# Controller.net
KiCad netlist of a schematic drawn in EasyEDA
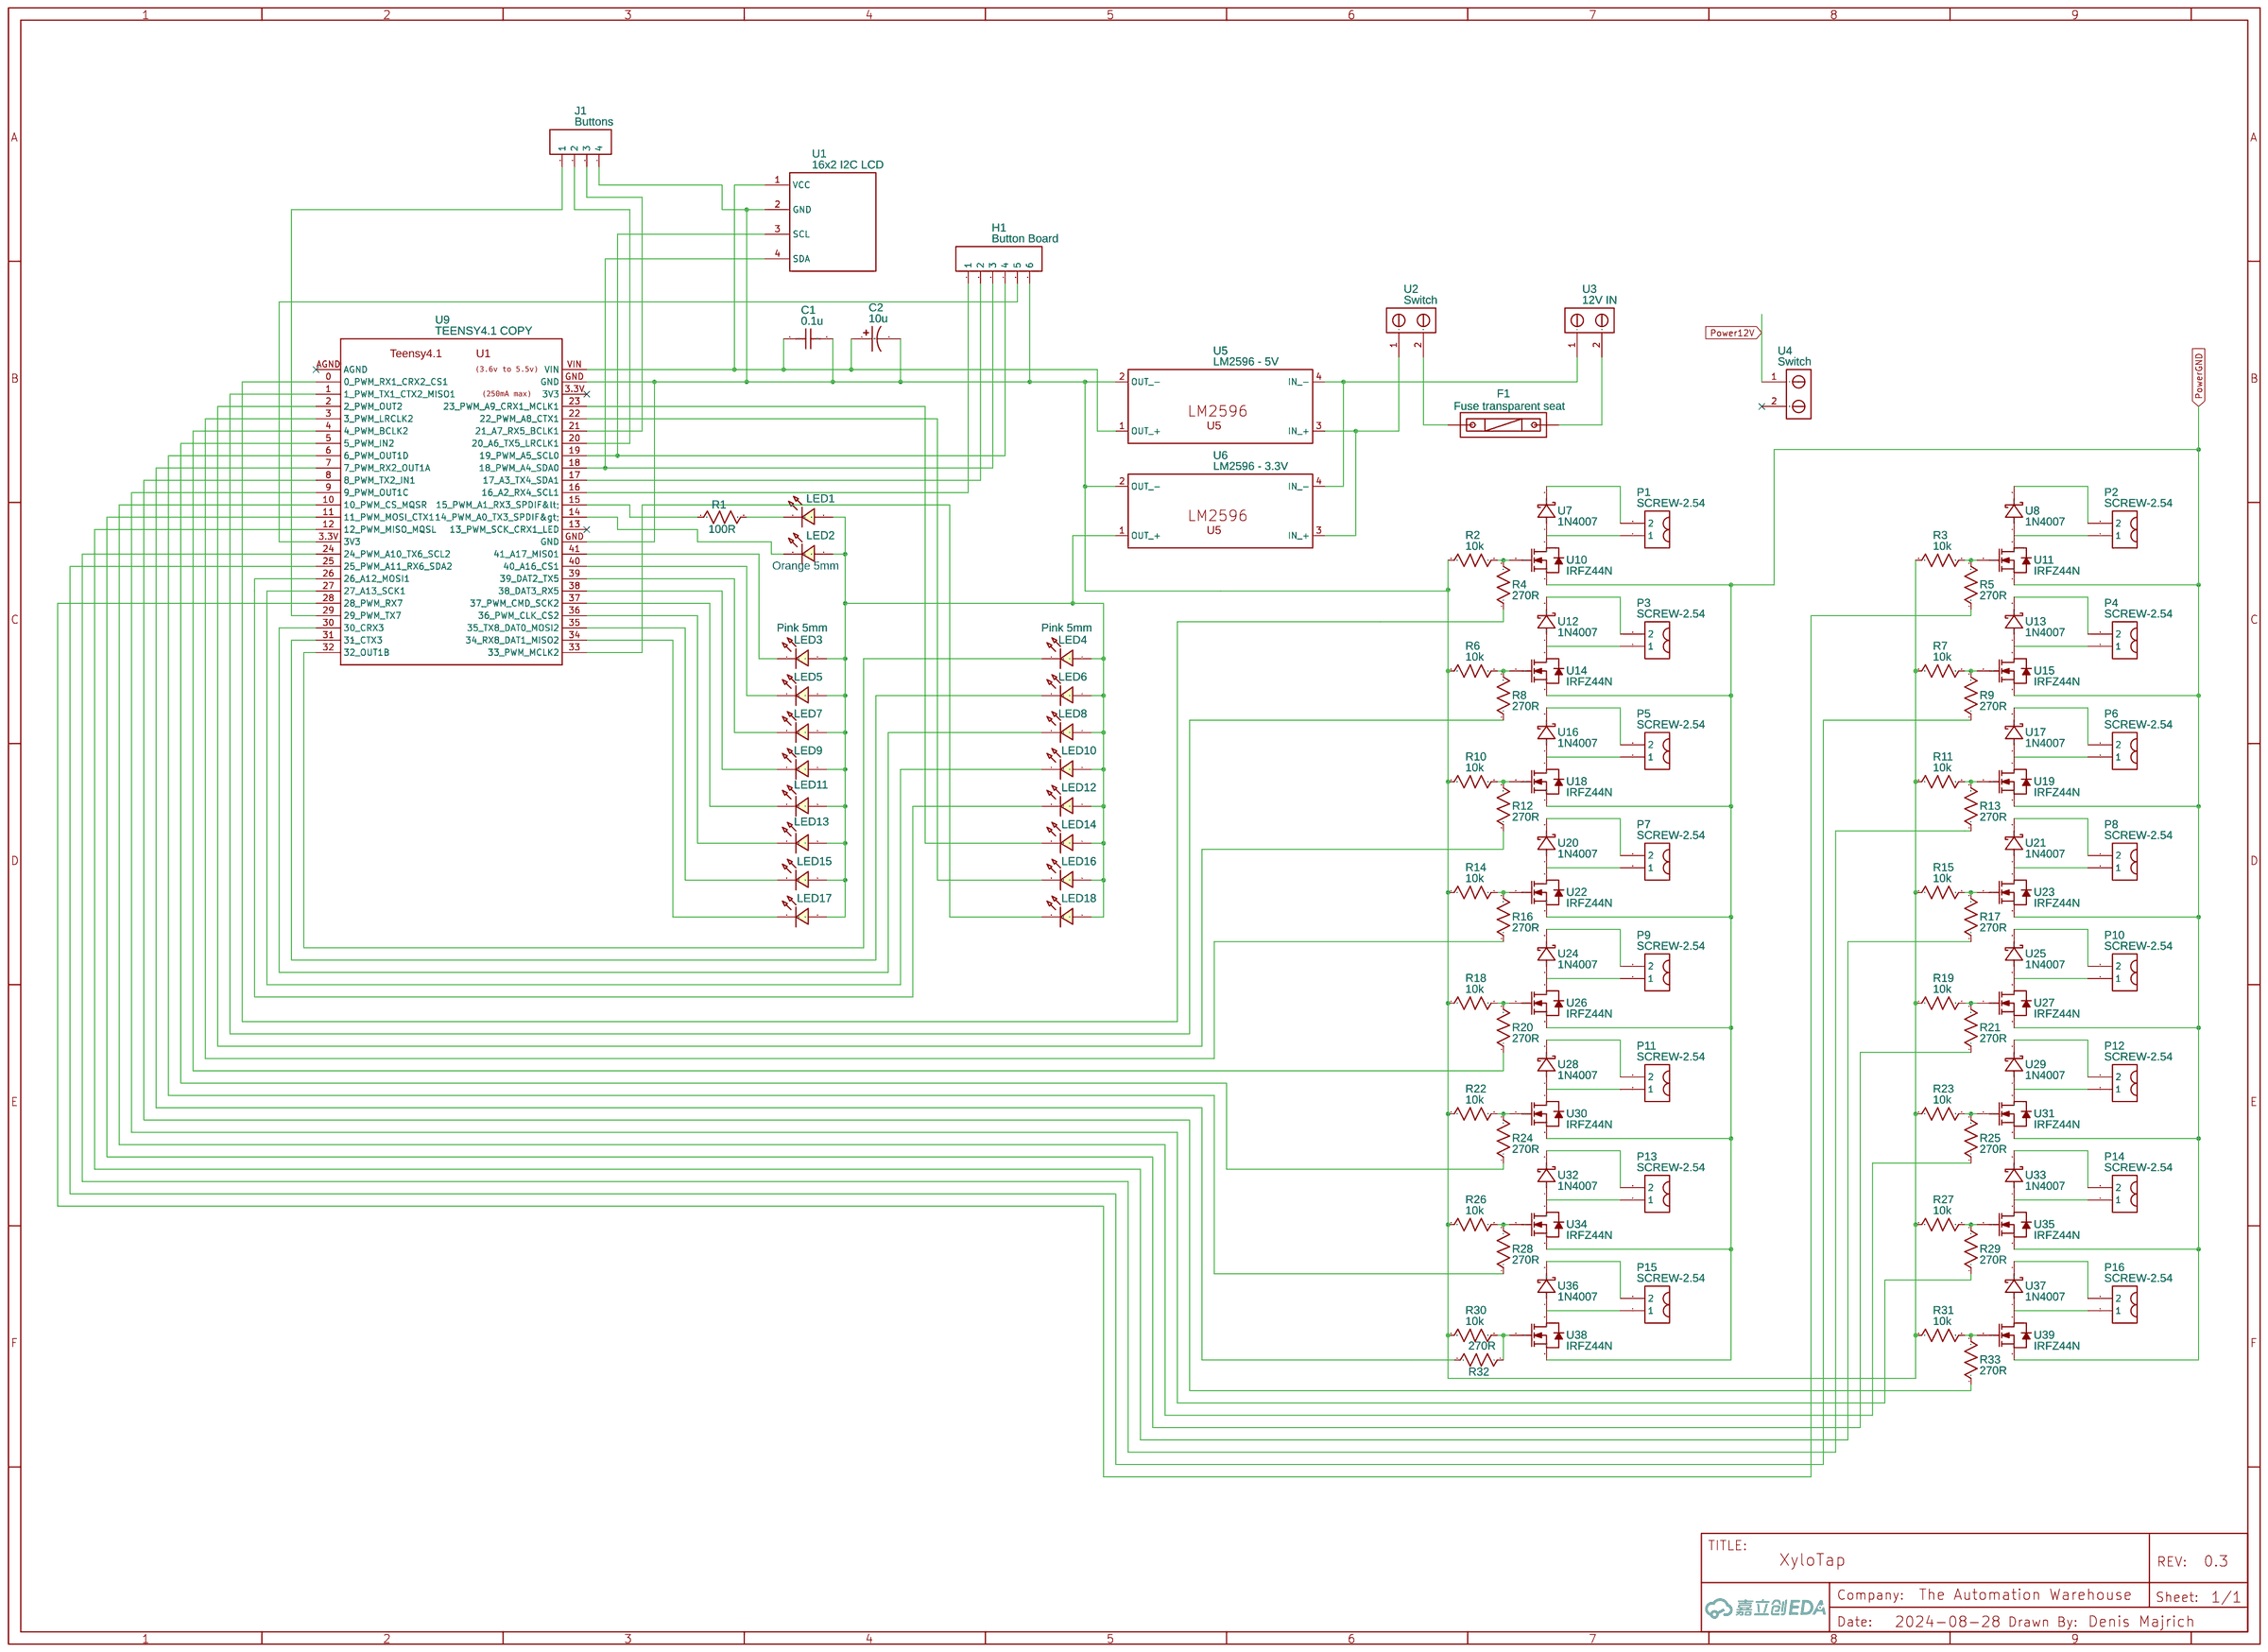
[diagram p0: schematic sheet]

(export (version "E")
  (design (tool "Eeschema 10.0.6"))
  (components
    (comp (ref "C1") (value "0.1u") (libsource (lib "") (part "C_RAD-0.1_US")))
    (comp (ref "C2") (value "10u") (libsource (lib "") (part "CE_TH_D5.0×F2.0_US")))
    (comp (ref "F1")
      (value "Fuse transparent seat")
      (fields (field (name "Manufacturer Part") "保险丝透明座") (field (name "Manufacturer") "xcfuse(旭程)"))
      (libsource (lib "") (part "Fuse transparent seat"))
    )
    (comp (ref "H1")
      (value "Button Board")
      (fields (field (name "BOM_Supplier Part") "C40877"))
      (libsource (lib "") (part "HDR-F-2.54_1x6"))
    )
    (comp (ref "J1")
      (value "Buttons")
      (fields (field (name "BOM_Supplier Part") "C124378"))
      (libsource (lib "") (part "HDR-M-2.54_1x4"))
    )
    (comp (ref "LED1") (value "Pink 5mm") (libsource (lib "") (part "LED-TH-5mm_B")))
    (comp (ref "LED2") (value "Pink 5mm") (libsource (lib "") (part "LED-TH-5mm_B")))
    (comp (ref "LED3") (value "Pink 5mm") (libsource (lib "") (part "LED-TH-5mm_B")))
    (comp (ref "LED4") (value "Pink 5mm") (libsource (lib "") (part "LED-TH-5mm_B")))
    (comp (ref "LED5") (value "Pink 5mm") (libsource (lib "") (part "LED-TH-5mm_B")))
    (comp (ref "LED6") (value "Pink 5mm") (libsource (lib "") (part "LED-TH-5mm_B")))
    (comp (ref "LED7") (value "Pink 5mm") (libsource (lib "") (part "LED-TH-5mm_B")))
    (comp (ref "LED8") (value "Pink 5mm") (libsource (lib "") (part "LED-TH-5mm_B")))
    (comp (ref "LED9") (value "Pink 5mm") (libsource (lib "") (part "LED-TH-5mm_B")))
    (comp (ref "LED10") (value "Pink 5mm") (libsource (lib "") (part "LED-TH-5mm_B")))
    (comp (ref "LED11") (value "Pink 5mm") (libsource (lib "") (part "LED-TH-5mm_B")))
    (comp (ref "LED12") (value "Pink 5mm") (libsource (lib "") (part "LED-TH-5mm_B")))
    (comp (ref "LED13") (value "Pink 5mm") (libsource (lib "") (part "LED-TH-5mm_B")))
    (comp (ref "LED14") (value "Pink 5mm") (libsource (lib "") (part "LED-TH-5mm_B")))
    (comp (ref "LED15") (value "Pink 5mm") (libsource (lib "") (part "LED-TH-5mm_B")))
    (comp (ref "LED16") (value "Pink 5mm") (libsource (lib "") (part "LED-TH-5mm_B")))
    (comp (ref "LED17") (value "Pink 5mm") (libsource (lib "") (part "LED-TH-5mm_B")))
    (comp (ref "LED18") (value "Pink 5mm") (libsource (lib "") (part "LED-TH-5mm_B")))
    (comp (ref "P1") (value "SCREW-2.54") (libsource (lib "") (part "PCBSCREW-2.54-2P")))
    (comp (ref "P2") (value "SCREW-2.54") (libsource (lib "") (part "PCBSCREW-2.54-2P")))
    (comp (ref "P3") (value "SCREW-2.54") (libsource (lib "") (part "PCBSCREW-2.54-2P")))
    (comp (ref "P4") (value "SCREW-2.54") (libsource (lib "") (part "PCBSCREW-2.54-2P")))
    (comp (ref "P5") (value "SCREW-2.54") (libsource (lib "") (part "PCBSCREW-2.54-2P")))
    (comp (ref "P6") (value "SCREW-2.54") (libsource (lib "") (part "PCBSCREW-2.54-2P")))
    (comp (ref "P7") (value "SCREW-2.54") (libsource (lib "") (part "PCBSCREW-2.54-2P")))
    (comp (ref "P8") (value "SCREW-2.54") (libsource (lib "") (part "PCBSCREW-2.54-2P")))
    (comp (ref "P9") (value "SCREW-2.54") (libsource (lib "") (part "PCBSCREW-2.54-2P")))
    (comp (ref "P10") (value "SCREW-2.54") (libsource (lib "") (part "PCBSCREW-2.54-2P")))
    (comp (ref "P11") (value "SCREW-2.54") (libsource (lib "") (part "PCBSCREW-2.54-2P")))
    (comp (ref "P12") (value "SCREW-2.54") (libsource (lib "") (part "PCBSCREW-2.54-2P")))
    (comp (ref "P13") (value "SCREW-2.54") (libsource (lib "") (part "PCBSCREW-2.54-2P")))
    (comp (ref "P14") (value "SCREW-2.54") (libsource (lib "") (part "PCBSCREW-2.54-2P")))
    (comp (ref "P15") (value "SCREW-2.54") (libsource (lib "") (part "PCBSCREW-2.54-2P")))
    (comp (ref "P16") (value "SCREW-2.54") (libsource (lib "") (part "PCBSCREW-2.54-2P")))
    (comp (ref "R1") (value "100R") (libsource (lib "") (part "R_AXIAL-0.4_US_1")))
    (comp (ref "R2") (value "10k") (libsource (lib "") (part "R_AXIAL-0.4_US_1")))
    (comp (ref "R3") (value "10k") (libsource (lib "") (part "R_AXIAL-0.4_US_1")))
    (comp (ref "R4") (value "270R") (libsource (lib "") (part "R_AXIAL-0.4_US")))
    (comp (ref "R5") (value "270R") (libsource (lib "") (part "R_AXIAL-0.4_US")))
    (comp (ref "R6") (value "10k") (libsource (lib "") (part "R_AXIAL-0.4_US_1")))
    (comp (ref "R7") (value "10k") (libsource (lib "") (part "R_AXIAL-0.4_US_1")))
    (comp (ref "R8") (value "270R") (libsource (lib "") (part "R_AXIAL-0.4_US")))
    (comp (ref "R9") (value "270R") (libsource (lib "") (part "R_AXIAL-0.4_US")))
    (comp (ref "R10") (value "10k") (libsource (lib "") (part "R_AXIAL-0.4_US_1")))
    (comp (ref "R11") (value "10k") (libsource (lib "") (part "R_AXIAL-0.4_US_1")))
    (comp (ref "R12") (value "270R") (libsource (lib "") (part "R_AXIAL-0.4_US")))
    (comp (ref "R13") (value "270R") (libsource (lib "") (part "R_AXIAL-0.4_US")))
    (comp (ref "R14") (value "10k") (libsource (lib "") (part "R_AXIAL-0.4_US_1")))
    (comp (ref "R15") (value "10k") (libsource (lib "") (part "R_AXIAL-0.4_US_1")))
    (comp (ref "R16") (value "270R") (libsource (lib "") (part "R_AXIAL-0.4_US")))
    (comp (ref "R17") (value "270R") (libsource (lib "") (part "R_AXIAL-0.4_US")))
    (comp (ref "R18") (value "10k") (libsource (lib "") (part "R_AXIAL-0.4_US_1")))
    (comp (ref "R19") (value "10k") (libsource (lib "") (part "R_AXIAL-0.4_US_1")))
    (comp (ref "R20") (value "270R") (libsource (lib "") (part "R_AXIAL-0.4_US")))
    (comp (ref "R21") (value "270R") (libsource (lib "") (part "R_AXIAL-0.4_US")))
    (comp (ref "R22") (value "10k") (libsource (lib "") (part "R_AXIAL-0.4_US_1")))
    (comp (ref "R23") (value "10k") (libsource (lib "") (part "R_AXIAL-0.4_US_1")))
    (comp (ref "R24") (value "270R") (libsource (lib "") (part "R_AXIAL-0.4_US")))
    (comp (ref "R25") (value "270R") (libsource (lib "") (part "R_AXIAL-0.4_US")))
    (comp (ref "R26") (value "10k") (libsource (lib "") (part "R_AXIAL-0.4_US_1")))
    (comp (ref "R27") (value "10k") (libsource (lib "") (part "R_AXIAL-0.4_US_1")))
    (comp (ref "R28") (value "270R") (libsource (lib "") (part "R_AXIAL-0.4_US")))
    (comp (ref "R29") (value "270R") (libsource (lib "") (part "R_AXIAL-0.4_US")))
    (comp (ref "R30") (value "10k") (libsource (lib "") (part "R_AXIAL-0.4_US_1")))
    (comp (ref "R31") (value "10k") (libsource (lib "") (part "R_AXIAL-0.4_US_1")))
    (comp (ref "R32") (value "270R") (libsource (lib "") (part "R_AXIAL-0.4_US_2")))
    (comp (ref "R33") (value "270R") (libsource (lib "") (part "R_AXIAL-0.4_US")))
    (comp (ref "U1") (value "16x2 I2C LCD") (libsource (lib "") (part "16x2 i2c LCD no mount on PCB")))
    (comp (ref "U2") (value "Switch") (libsource (lib "") (part "Terminal_x2_5mm")))
    (comp (ref "U3") (value "12V IN") (libsource (lib "") (part "Terminal_x2_5mm")))
    (comp (ref "U4") (value "Switch") (libsource (lib "") (part "Terminal_x2_5mm_1")))
    (comp (ref "U5")
      (value "LM2596 - 5V")
      (fields (field (name "BOM_Manufacturer Part") "LM2596ALEX"))
      (libsource (lib "") (part "LM2596ALEX"))
    )
    (comp (ref "U6")
      (value "LM2596 - 3.3V")
      (fields (field (name "BOM_Manufacturer Part") "LM2596ALEX"))
      (libsource (lib "") (part "LM2596ALEX"))
    )
    (comp (ref "U7")
      (value "1N4007")
      (fields (field (name "Manufacturer Part") "1N4007-DIODE"))
      (libsource (lib "") (part "1N4007-DIODE"))
    )
    (comp (ref "U8")
      (value "1N4007")
      (fields (field (name "Manufacturer Part") "1N4007-DIODE"))
      (libsource (lib "") (part "1N4007-DIODE"))
    )
    (comp (ref "U9")
      (value "TEENSY4.1 COPY")
      (fields (field (name "BOM_Manufacturer Part") "Teensy4.1"))
      (libsource (lib "") (part "TEENSY4.1 COPY"))
    )
    (comp (ref "U10")
      (value "IRFZ44N")
      (fields (field (name "Manufacturer") "minos(迈诺斯)"))
      (libsource (lib "") (part "IRFZ44N"))
    )
    (comp (ref "U11")
      (value "IRFZ44N")
      (fields (field (name "Manufacturer") "minos(迈诺斯)"))
      (libsource (lib "") (part "IRFZ44N"))
    )
    (comp (ref "U12")
      (value "1N4007")
      (fields (field (name "Manufacturer Part") "1N4007-DIODE"))
      (libsource (lib "") (part "1N4007-DIODE"))
    )
    (comp (ref "U13")
      (value "1N4007")
      (fields (field (name "Manufacturer Part") "1N4007-DIODE"))
      (libsource (lib "") (part "1N4007-DIODE"))
    )
    (comp (ref "U14")
      (value "IRFZ44N")
      (fields (field (name "Manufacturer") "minos(迈诺斯)"))
      (libsource (lib "") (part "IRFZ44N"))
    )
    (comp (ref "U15")
      (value "IRFZ44N")
      (fields (field (name "Manufacturer") "minos(迈诺斯)"))
      (libsource (lib "") (part "IRFZ44N"))
    )
    (comp (ref "U16")
      (value "1N4007")
      (fields (field (name "Manufacturer Part") "1N4007-DIODE"))
      (libsource (lib "") (part "1N4007-DIODE"))
    )
    (comp (ref "U17")
      (value "1N4007")
      (fields (field (name "Manufacturer Part") "1N4007-DIODE"))
      (libsource (lib "") (part "1N4007-DIODE"))
    )
    (comp (ref "U18")
      (value "IRFZ44N")
      (fields (field (name "Manufacturer") "minos(迈诺斯)"))
      (libsource (lib "") (part "IRFZ44N"))
    )
    (comp (ref "U19")
      (value "IRFZ44N")
      (fields (field (name "Manufacturer") "minos(迈诺斯)"))
      (libsource (lib "") (part "IRFZ44N"))
    )
    (comp (ref "U20")
      (value "1N4007")
      (fields (field (name "Manufacturer Part") "1N4007-DIODE"))
      (libsource (lib "") (part "1N4007-DIODE"))
    )
    (comp (ref "U21")
      (value "1N4007")
      (fields (field (name "Manufacturer Part") "1N4007-DIODE"))
      (libsource (lib "") (part "1N4007-DIODE"))
    )
    (comp (ref "U22")
      (value "IRFZ44N")
      (fields (field (name "Manufacturer") "minos(迈诺斯)"))
      (libsource (lib "") (part "IRFZ44N"))
    )
    (comp (ref "U23")
      (value "IRFZ44N")
      (fields (field (name "Manufacturer") "minos(迈诺斯)"))
      (libsource (lib "") (part "IRFZ44N"))
    )
    (comp (ref "U24")
      (value "1N4007")
      (fields (field (name "Manufacturer Part") "1N4007-DIODE"))
      (libsource (lib "") (part "1N4007-DIODE"))
    )
    (comp (ref "U25")
      (value "1N4007")
      (fields (field (name "Manufacturer Part") "1N4007-DIODE"))
      (libsource (lib "") (part "1N4007-DIODE"))
    )
    (comp (ref "U26")
      (value "IRFZ44N")
      (fields (field (name "Manufacturer") "minos(迈诺斯)"))
      (libsource (lib "") (part "IRFZ44N"))
    )
    (comp (ref "U27")
      (value "IRFZ44N")
      (fields (field (name "Manufacturer") "minos(迈诺斯)"))
      (libsource (lib "") (part "IRFZ44N"))
    )
    (comp (ref "U28")
      (value "1N4007")
      (fields (field (name "Manufacturer Part") "1N4007-DIODE"))
      (libsource (lib "") (part "1N4007-DIODE"))
    )
    (comp (ref "U29")
      (value "1N4007")
      (fields (field (name "Manufacturer Part") "1N4007-DIODE"))
      (libsource (lib "") (part "1N4007-DIODE"))
    )
    (comp (ref "U30")
      (value "IRFZ44N")
      (fields (field (name "Manufacturer") "minos(迈诺斯)"))
      (libsource (lib "") (part "IRFZ44N"))
    )
    (comp (ref "U31")
      (value "IRFZ44N")
      (fields (field (name "Manufacturer") "minos(迈诺斯)"))
      (libsource (lib "") (part "IRFZ44N"))
    )
    (comp (ref "U32")
      (value "1N4007")
      (fields (field (name "Manufacturer Part") "1N4007-DIODE"))
      (libsource (lib "") (part "1N4007-DIODE"))
    )
    (comp (ref "U33")
      (value "1N4007")
      (fields (field (name "Manufacturer Part") "1N4007-DIODE"))
      (libsource (lib "") (part "1N4007-DIODE"))
    )
    (comp (ref "U34")
      (value "IRFZ44N")
      (fields (field (name "Manufacturer") "minos(迈诺斯)"))
      (libsource (lib "") (part "IRFZ44N"))
    )
    (comp (ref "U35")
      (value "IRFZ44N")
      (fields (field (name "Manufacturer") "minos(迈诺斯)"))
      (libsource (lib "") (part "IRFZ44N"))
    )
    (comp (ref "U36")
      (value "1N4007")
      (fields (field (name "Manufacturer Part") "1N4007-DIODE"))
      (libsource (lib "") (part "1N4007-DIODE"))
    )
    (comp (ref "U37")
      (value "1N4007")
      (fields (field (name "Manufacturer Part") "1N4007-DIODE"))
      (libsource (lib "") (part "1N4007-DIODE"))
    )
    (comp (ref "U38")
      (value "IRFZ44N")
      (fields (field (name "Manufacturer") "minos(迈诺斯)"))
      (libsource (lib "") (part "IRFZ44N"))
    )
    (comp (ref "U39")
      (value "IRFZ44N")
      (fields (field (name "Manufacturer") "minos(迈诺斯)"))
      (libsource (lib "") (part "IRFZ44N"))
    )
  )
  (nets
    (net (code "1") (name "Net-(F1-Pad1)") (class "Default")
      (node (ref "F1") (pin "1") (pinfunction "1_1") (pintype "unspecified"))
      (node (ref "U3") (pin "2") (pinfunction "2_2") (pintype "unspecified"))
    )
    (net (code "2") (name "Net-(F1-Pad2)") (class "Default")
      (node (ref "F1") (pin "2") (pinfunction "2_2") (pintype "unspecified"))
      (node (ref "U2") (pin "2") (pinfunction "2_2") (pintype "unspecified"))
    )
    (net (code "3") (name "Net-(LED1-Pad2)") (class "Default")
      (node (ref "LED1") (pin "2") (pinfunction "2_2") (pintype "unspecified"))
      (node (ref "R1") (pin "2") (pinfunction "2_2") (pintype "unspecified"))
    )
    (net (code "4") (name "Net-(U1-GND)") (class "Default")
      (node (ref "C1") (pin "2") (pinfunction "2_2") (pintype "unspecified"))
      (node (ref "C2") (pin "2") (pinfunction "2_2") (pintype "unspecified"))
      (node (ref "H1") (pin "6") (pinfunction "6_6") (pintype "input"))
      (node (ref "J1") (pin "4") (pinfunction "4_4") (pintype "unspecified"))
      (node (ref "R10") (pin "1") (pinfunction "1_1") (pintype "unspecified"))
      (node (ref "R11") (pin "1") (pinfunction "1_1") (pintype "unspecified"))
      (node (ref "R14") (pin "1") (pinfunction "1_1") (pintype "unspecified"))
      (node (ref "R15") (pin "1") (pinfunction "1_1") (pintype "unspecified"))
      (node (ref "R18") (pin "1") (pinfunction "1_1") (pintype "unspecified"))
      (node (ref "R19") (pin "1") (pinfunction "1_1") (pintype "unspecified"))
      (node (ref "R2") (pin "1") (pinfunction "1_1") (pintype "unspecified"))
      (node (ref "R22") (pin "1") (pinfunction "1_1") (pintype "unspecified"))
      (node (ref "R23") (pin "1") (pinfunction "1_1") (pintype "unspecified"))
      (node (ref "R26") (pin "1") (pinfunction "1_1") (pintype "unspecified"))
      (node (ref "R27") (pin "1") (pinfunction "1_1") (pintype "unspecified"))
      (node (ref "R3") (pin "1") (pinfunction "1_1") (pintype "unspecified"))
      (node (ref "R30") (pin "1") (pinfunction "1_1") (pintype "unspecified"))
      (node (ref "R31") (pin "1") (pinfunction "1_1") (pintype "unspecified"))
      (node (ref "R6") (pin "1") (pinfunction "1_1") (pintype "unspecified"))
      (node (ref "R7") (pin "1") (pinfunction "1_1") (pintype "unspecified"))
      (node (ref "U1") (pin "2") (pinfunction "GND_2") (pintype "unspecified"))
      (node (ref "U5") (pin "2") (pinfunction "OUT_-_2") (pintype "unspecified"))
      (node (ref "U6") (pin "2") (pinfunction "OUT_-_2") (pintype "unspecified"))
      (node (ref "U9") (pin "GND") (pinfunction "GND_GND") (pintype "bidirectional"))
    )
    (net (code "5") (name "Net-(U1-SCL)") (class "Default")
      (node (ref "H1") (pin "4") (pinfunction "4_4") (pintype "input"))
      (node (ref "U1") (pin "3") (pinfunction "SCL_3") (pintype "unspecified"))
      (node (ref "U9") (pin "19") (pinfunction "19_PWM_A5_SCL0_19") (pintype "bidirectional"))
    )
    (net (code "6") (name "Net-(U1-SDA)") (class "Default")
      (node (ref "H1") (pin "3") (pinfunction "3_3") (pintype "input"))
      (node (ref "U1") (pin "4") (pinfunction "SDA_4") (pintype "unspecified"))
      (node (ref "U9") (pin "18") (pinfunction "18_PWM_A4_SDA0_18") (pintype "bidirectional"))
    )
    (net (code "7") (name "Net-(U1-VCC)") (class "Default")
      (node (ref "C1") (pin "1") (pinfunction "1_1") (pintype "unspecified"))
      (node (ref "C2") (pin "1") (pinfunction "1_1") (pintype "unspecified"))
      (node (ref "U1") (pin "1") (pinfunction "VCC_1") (pintype "unspecified"))
      (node (ref "U5") (pin "1") (pinfunction "OUT_+_1") (pintype "unspecified"))
      (node (ref "U9") (pin "VIN") (pinfunction "VIN_VIN") (pintype "bidirectional"))
    )
    (net (code "8") (name "Net-(U5-IN_+)") (class "Default")
      (node (ref "U2") (pin "1") (pinfunction "1_1") (pintype "unspecified"))
      (node (ref "U5") (pin "3") (pinfunction "IN_+_3") (pintype "unspecified"))
      (node (ref "U6") (pin "3") (pinfunction "IN_+_3") (pintype "unspecified"))
    )
    (net (code "9") (name "Net-(U5-IN_-)") (class "Default")
      (node (ref "U3") (pin "1") (pinfunction "1_1") (pintype "unspecified"))
      (node (ref "U5") (pin "4") (pinfunction "IN_-_4") (pintype "unspecified"))
      (node (ref "U6") (pin "4") (pinfunction "IN_-_4") (pintype "unspecified"))
    )
    (net (code "10") (name "Net-(U6-OUT_+)") (class "Default")
      (node (ref "LED1") (pin "1") (pinfunction "1_1") (pintype "unspecified"))
      (node (ref "LED10") (pin "1") (pinfunction "1_1") (pintype "unspecified"))
      (node (ref "LED11") (pin "1") (pinfunction "1_1") (pintype "unspecified"))
      (node (ref "LED12") (pin "1") (pinfunction "1_1") (pintype "unspecified"))
      (node (ref "LED13") (pin "1") (pinfunction "1_1") (pintype "unspecified"))
      (node (ref "LED14") (pin "1") (pinfunction "1_1") (pintype "unspecified"))
      (node (ref "LED15") (pin "1") (pinfunction "1_1") (pintype "unspecified"))
      (node (ref "LED16") (pin "1") (pinfunction "1_1") (pintype "unspecified"))
      (node (ref "LED17") (pin "1") (pinfunction "1_1") (pintype "unspecified"))
      (node (ref "LED18") (pin "1") (pinfunction "1_1") (pintype "unspecified"))
      (node (ref "LED2") (pin "1") (pinfunction "1_1") (pintype "unspecified"))
      (node (ref "LED3") (pin "1") (pinfunction "1_1") (pintype "unspecified"))
      (node (ref "LED4") (pin "1") (pinfunction "1_1") (pintype "unspecified"))
      (node (ref "LED5") (pin "1") (pinfunction "1_1") (pintype "unspecified"))
      (node (ref "LED6") (pin "1") (pinfunction "1_1") (pintype "unspecified"))
      (node (ref "LED7") (pin "1") (pinfunction "1_1") (pintype "unspecified"))
      (node (ref "LED8") (pin "1") (pinfunction "1_1") (pintype "unspecified"))
      (node (ref "LED9") (pin "1") (pinfunction "1_1") (pintype "unspecified"))
      (node (ref "U6") (pin "1") (pinfunction "OUT_+_1") (pintype "unspecified"))
    )
    (net (code "11") (name "Net-(U7-K)") (class "Default")
      (node (ref "P1") (pin "2") (pinfunction "2_2") (pintype "unspecified"))
      (node (ref "U7") (pin "2") (pinfunction "K_2") (pintype "unspecified"))
    )
    (net (code "12") (name "Net-(U8-K)") (class "Default")
      (node (ref "P2") (pin "2") (pinfunction "2_2") (pintype "unspecified"))
      (node (ref "U8") (pin "2") (pinfunction "K_2") (pintype "unspecified"))
    )
    (net (code "13") (name "Net-(U9-0_PWM_RX1_CRX2_CS1)") (class "Default")
      (node (ref "R4") (pin "1") (pinfunction "1_1") (pintype "unspecified"))
      (node (ref "U9") (pin "0") (pinfunction "0_PWM_RX1_CRX2_CS1_0") (pintype "bidirectional"))
    )
    (net (code "14") (name "Net-(U9-1_PWM_TX1_CTX2_MISO1)") (class "Default")
      (node (ref "R8") (pin "1") (pinfunction "1_1") (pintype "unspecified"))
      (node (ref "U9") (pin "1") (pinfunction "1_PWM_TX1_CTX2_MISO1_1") (pintype "bidirectional"))
    )
    (net (code "15") (name "Net-(U9-2_PWM_OUT2)") (class "Default")
      (node (ref "R12") (pin "1") (pinfunction "1_1") (pintype "unspecified"))
      (node (ref "U9") (pin "2") (pinfunction "2_PWM_OUT2_2") (pintype "bidirectional"))
    )
    (net (code "16") (name "Net-(U9-3V3)") (class "Default")
      (node (ref "H1") (pin "5") (pinfunction "5_5") (pintype "input"))
      (node (ref "U9") (pin "3.3V") (pinfunction "3V3_3.3V") (pintype "bidirectional"))
    )
    (net (code "17") (name "Net-(U9-3_PWM_LRCLK2)") (class "Default")
      (node (ref "R16") (pin "1") (pinfunction "1_1") (pintype "unspecified"))
      (node (ref "U9") (pin "3") (pinfunction "3_PWM_LRCLK2_3") (pintype "bidirectional"))
    )
    (net (code "18") (name "Net-(U9-4_PWM_BCLK2)") (class "Default")
      (node (ref "R20") (pin "1") (pinfunction "1_1") (pintype "unspecified"))
      (node (ref "U9") (pin "4") (pinfunction "4_PWM_BCLK2_4") (pintype "bidirectional"))
    )
    (net (code "19") (name "Net-(U9-5_PWM_IN2)") (class "Default")
      (node (ref "R24") (pin "1") (pinfunction "1_1") (pintype "unspecified"))
      (node (ref "U9") (pin "5") (pinfunction "5_PWM_IN2_5") (pintype "bidirectional"))
    )
    (net (code "20") (name "Net-(U9-6_PWM_OUT1D)") (class "Default")
      (node (ref "R28") (pin "1") (pinfunction "1_1") (pintype "unspecified"))
      (node (ref "U9") (pin "6") (pinfunction "6_PWM_OUT1D_6") (pintype "bidirectional"))
    )
    (net (code "21") (name "Net-(U9-7_PWM_RX2_OUT1A)") (class "Default")
      (node (ref "R32") (pin "2") (pinfunction "2_2") (pintype "unspecified"))
      (node (ref "U9") (pin "7") (pinfunction "7_PWM_RX2_OUT1A_7") (pintype "bidirectional"))
    )
    (net (code "22") (name "Net-(U9-8_PWM_TX2_IN1)") (class "Default")
      (node (ref "R33") (pin "1") (pinfunction "1_1") (pintype "unspecified"))
      (node (ref "U9") (pin "8") (pinfunction "8_PWM_TX2_IN1_8") (pintype "bidirectional"))
    )
    (net (code "23") (name "Net-(U9-9_PWM_OUT1C)") (class "Default")
      (node (ref "R29") (pin "1") (pinfunction "1_1") (pintype "unspecified"))
      (node (ref "U9") (pin "9") (pinfunction "9_PWM_OUT1C_9") (pintype "bidirectional"))
    )
    (net (code "24") (name "Net-(U9-10_PWM_CS_MQSR)") (class "Default")
      (node (ref "R25") (pin "1") (pinfunction "1_1") (pintype "unspecified"))
      (node (ref "U9") (pin "10") (pinfunction "10_PWM_CS_MQSR_10") (pintype "bidirectional"))
    )
    (net (code "25") (name "Net-(U9-11_PWM_MOSI_CTX1)") (class "Default")
      (node (ref "R21") (pin "1") (pinfunction "1_1") (pintype "unspecified"))
      (node (ref "U9") (pin "11") (pinfunction "11_PWM_MOSI_CTX1_11") (pintype "bidirectional"))
    )
    (net (code "26") (name "Net-(U9-12_PWM_MISO_MQSL)") (class "Default")
      (node (ref "R17") (pin "1") (pinfunction "1_1") (pintype "unspecified"))
      (node (ref "U9") (pin "12") (pinfunction "12_PWM_MISO_MQSL_12") (pintype "bidirectional"))
    )
    (net (code "27") (name "Net-(U9-14_PWM_A0_TX3_SPDIF&gt;)") (class "Default")
      (node (ref "LED2") (pin "2") (pinfunction "2_2") (pintype "unspecified"))
      (node (ref "U9") (pin "14") (pinfunction "14_PWM_A0_TX3_SPDIF&gt;_14") (pintype "bidirectional"))
    )
    (net (code "28") (name "Net-(U9-15_PWM_A1_RX3_SPDIF&lt;)") (class "Default")
      (node (ref "R1") (pin "1") (pinfunction "1_1") (pintype "unspecified"))
      (node (ref "U9") (pin "15") (pinfunction "15_PWM_A1_RX3_SPDIF&lt;_15") (pintype "bidirectional"))
    )
    (net (code "29") (name "Net-(U9-16_A2_RX4_SCL1)") (class "Default")
      (node (ref "H1") (pin "1") (pinfunction "1_1") (pintype "input"))
      (node (ref "U9") (pin "16") (pinfunction "16_A2_RX4_SCL1_16") (pintype "bidirectional"))
    )
    (net (code "30") (name "Net-(U9-17_A3_TX4_SDA1)") (class "Default")
      (node (ref "H1") (pin "2") (pinfunction "2_2") (pintype "input"))
      (node (ref "U9") (pin "17") (pinfunction "17_A3_TX4_SDA1_17") (pintype "bidirectional"))
    )
    (net (code "31") (name "Net-(U9-20_A6_TX5_LRCLK1)") (class "Default")
      (node (ref "J1") (pin "2") (pinfunction "2_2") (pintype "unspecified"))
      (node (ref "U9") (pin "20") (pinfunction "20_A6_TX5_LRCLK1_20") (pintype "bidirectional"))
    )
    (net (code "32") (name "Net-(U9-21_A7_RX5_BCLK1)") (class "Default")
      (node (ref "J1") (pin "3") (pinfunction "3_3") (pintype "unspecified"))
      (node (ref "U9") (pin "21") (pinfunction "21_A7_RX5_BCLK1_21") (pintype "bidirectional"))
    )
    (net (code "33") (name "Net-(U9-22_PWM_A8_CTX1)") (class "Default")
      (node (ref "LED16") (pin "2") (pinfunction "2_2") (pintype "unspecified"))
      (node (ref "U9") (pin "22") (pinfunction "22_PWM_A8_CTX1_22") (pintype "bidirectional"))
    )
    (net (code "34") (name "Net-(U9-23_PWM_A9_CRX1_MCLK1)") (class "Default")
      (node (ref "LED14") (pin "2") (pinfunction "2_2") (pintype "unspecified"))
      (node (ref "U9") (pin "23") (pinfunction "23_PWM_A9_CRX1_MCLK1_23") (pintype "bidirectional"))
    )
    (net (code "35") (name "Net-(U9-24_PWM_A10_TX6_SCL2)") (class "Default")
      (node (ref "R13") (pin "1") (pinfunction "1_1") (pintype "unspecified"))
      (node (ref "U9") (pin "24") (pinfunction "24_PWM_A10_TX6_SCL2_24") (pintype "bidirectional"))
    )
    (net (code "36") (name "Net-(U9-25_PWM_A11_RX6_SDA2)") (class "Default")
      (node (ref "R9") (pin "1") (pinfunction "1_1") (pintype "unspecified"))
      (node (ref "U9") (pin "25") (pinfunction "25_PWM_A11_RX6_SDA2_25") (pintype "bidirectional"))
    )
    (net (code "37") (name "Net-(U9-26_A12_MOSI1)") (class "Default")
      (node (ref "LED12") (pin "2") (pinfunction "2_2") (pintype "unspecified"))
      (node (ref "U9") (pin "26") (pinfunction "26_A12_MOSI1_26") (pintype "bidirectional"))
    )
    (net (code "38") (name "Net-(U9-27_A13_SCK1)") (class "Default")
      (node (ref "LED10") (pin "2") (pinfunction "2_2") (pintype "unspecified"))
      (node (ref "U9") (pin "27") (pinfunction "27_A13_SCK1_27") (pintype "bidirectional"))
    )
    (net (code "39") (name "Net-(U9-28_PWM_RX7)") (class "Default")
      (node (ref "R5") (pin "1") (pinfunction "1_1") (pintype "unspecified"))
      (node (ref "U9") (pin "28") (pinfunction "28_PWM_RX7_28") (pintype "bidirectional"))
    )
    (net (code "40") (name "Net-(U9-29_PWM_TX7)") (class "Default")
      (node (ref "J1") (pin "1") (pinfunction "1_1") (pintype "unspecified"))
      (node (ref "U9") (pin "29") (pinfunction "29_PWM_TX7_29") (pintype "bidirectional"))
    )
    (net (code "41") (name "Net-(U9-30_CRX3)") (class "Default")
      (node (ref "LED8") (pin "2") (pinfunction "2_2") (pintype "unspecified"))
      (node (ref "U9") (pin "30") (pinfunction "30_CRX3_30") (pintype "bidirectional"))
    )
    (net (code "42") (name "Net-(U9-31_CTX3)") (class "Default")
      (node (ref "LED6") (pin "2") (pinfunction "2_2") (pintype "unspecified"))
      (node (ref "U9") (pin "31") (pinfunction "31_CTX3_31") (pintype "bidirectional"))
    )
    (net (code "43") (name "Net-(U9-32_OUT1B)") (class "Default")
      (node (ref "LED4") (pin "2") (pinfunction "2_2") (pintype "unspecified"))
      (node (ref "U9") (pin "32") (pinfunction "32_OUT1B_32") (pintype "bidirectional"))
    )
    (net (code "44") (name "Net-(U9-33_PWM_MCLK2)") (class "Default")
      (node (ref "LED18") (pin "2") (pinfunction "2_2") (pintype "unspecified"))
      (node (ref "U9") (pin "33") (pinfunction "33_PWM_MCLK2_33") (pintype "bidirectional"))
    )
    (net (code "45") (name "Net-(U9-34_RX8_DAT1_MISO2)") (class "Default")
      (node (ref "LED17") (pin "2") (pinfunction "2_2") (pintype "unspecified"))
      (node (ref "U9") (pin "34") (pinfunction "34_RX8_DAT1_MISO2_34") (pintype "bidirectional"))
    )
    (net (code "46") (name "Net-(U9-35_TX8_DAT0_MOSI2)") (class "Default")
      (node (ref "LED15") (pin "2") (pinfunction "2_2") (pintype "unspecified"))
      (node (ref "U9") (pin "35") (pinfunction "35_TX8_DAT0_MOSI2_35") (pintype "bidirectional"))
    )
    (net (code "47") (name "Net-(U9-36_PWM_CLK_CS2)") (class "Default")
      (node (ref "LED13") (pin "2") (pinfunction "2_2") (pintype "unspecified"))
      (node (ref "U9") (pin "36") (pinfunction "36_PWM_CLK_CS2_36") (pintype "bidirectional"))
    )
    (net (code "48") (name "Net-(U9-37_PWM_CMD_SCK2)") (class "Default")
      (node (ref "LED11") (pin "2") (pinfunction "2_2") (pintype "unspecified"))
      (node (ref "U9") (pin "37") (pinfunction "37_PWM_CMD_SCK2_37") (pintype "bidirectional"))
    )
    (net (code "49") (name "Net-(U9-38_DAT3_RX5)") (class "Default")
      (node (ref "LED9") (pin "2") (pinfunction "2_2") (pintype "unspecified"))
      (node (ref "U9") (pin "38") (pinfunction "38_DAT3_RX5_38") (pintype "bidirectional"))
    )
    (net (code "50") (name "Net-(U9-39_DAT2_TX5)") (class "Default")
      (node (ref "LED7") (pin "2") (pinfunction "2_2") (pintype "unspecified"))
      (node (ref "U9") (pin "39") (pinfunction "39_DAT2_TX5_39") (pintype "bidirectional"))
    )
    (net (code "51") (name "Net-(U9-40_A16_CS1)") (class "Default")
      (node (ref "LED5") (pin "2") (pinfunction "2_2") (pintype "unspecified"))
      (node (ref "U9") (pin "40") (pinfunction "40_A16_CS1_40") (pintype "bidirectional"))
    )
    (net (code "52") (name "Net-(U9-41_A17_MIS01)") (class "Default")
      (node (ref "LED3") (pin "2") (pinfunction "2_2") (pintype "unspecified"))
      (node (ref "U9") (pin "41") (pinfunction "41_A17_MIS01_41") (pintype "bidirectional"))
    )
    (net (code "53") (name "Net-(U10-D)") (class "Default")
      (node (ref "P1") (pin "1") (pinfunction "1_1") (pintype "unspecified"))
      (node (ref "U10") (pin "2") (pinfunction "D_2") (pintype "unspecified"))
      (node (ref "U7") (pin "1") (pinfunction "A_1") (pintype "unspecified"))
    )
    (net (code "54") (name "Net-(U10-G)") (class "Default")
      (node (ref "R2") (pin "2") (pinfunction "2_2") (pintype "unspecified"))
      (node (ref "R4") (pin "2") (pinfunction "2_2") (pintype "unspecified"))
      (node (ref "U10") (pin "1") (pinfunction "G_1") (pintype "unspecified"))
    )
    (net (code "55") (name "Net-(U11-D)") (class "Default")
      (node (ref "P2") (pin "1") (pinfunction "1_1") (pintype "unspecified"))
      (node (ref "U11") (pin "2") (pinfunction "D_2") (pintype "unspecified"))
      (node (ref "U8") (pin "1") (pinfunction "A_1") (pintype "unspecified"))
    )
    (net (code "56") (name "Net-(U11-G)") (class "Default")
      (node (ref "R3") (pin "2") (pinfunction "2_2") (pintype "unspecified"))
      (node (ref "R5") (pin "2") (pinfunction "2_2") (pintype "unspecified"))
      (node (ref "U11") (pin "1") (pinfunction "G_1") (pintype "unspecified"))
    )
    (net (code "57") (name "Net-(U12-A)") (class "Default")
      (node (ref "P3") (pin "1") (pinfunction "1_1") (pintype "unspecified"))
      (node (ref "U12") (pin "1") (pinfunction "A_1") (pintype "unspecified"))
      (node (ref "U14") (pin "2") (pinfunction "D_2") (pintype "unspecified"))
    )
    (net (code "58") (name "Net-(U12-K)") (class "Default")
      (node (ref "P3") (pin "2") (pinfunction "2_2") (pintype "unspecified"))
      (node (ref "U12") (pin "2") (pinfunction "K_2") (pintype "unspecified"))
    )
    (net (code "59") (name "Net-(U13-A)") (class "Default")
      (node (ref "P4") (pin "1") (pinfunction "1_1") (pintype "unspecified"))
      (node (ref "U13") (pin "1") (pinfunction "A_1") (pintype "unspecified"))
      (node (ref "U15") (pin "2") (pinfunction "D_2") (pintype "unspecified"))
    )
    (net (code "60") (name "Net-(U13-K)") (class "Default")
      (node (ref "P4") (pin "2") (pinfunction "2_2") (pintype "unspecified"))
      (node (ref "U13") (pin "2") (pinfunction "K_2") (pintype "unspecified"))
    )
    (net (code "61") (name "Net-(U14-G)") (class "Default")
      (node (ref "R6") (pin "2") (pinfunction "2_2") (pintype "unspecified"))
      (node (ref "R8") (pin "2") (pinfunction "2_2") (pintype "unspecified"))
      (node (ref "U14") (pin "1") (pinfunction "G_1") (pintype "unspecified"))
    )
    (net (code "62") (name "Net-(U15-G)") (class "Default")
      (node (ref "R7") (pin "2") (pinfunction "2_2") (pintype "unspecified"))
      (node (ref "R9") (pin "2") (pinfunction "2_2") (pintype "unspecified"))
      (node (ref "U15") (pin "1") (pinfunction "G_1") (pintype "unspecified"))
    )
    (net (code "63") (name "Net-(U16-A)") (class "Default")
      (node (ref "P5") (pin "1") (pinfunction "1_1") (pintype "unspecified"))
      (node (ref "U16") (pin "1") (pinfunction "A_1") (pintype "unspecified"))
      (node (ref "U18") (pin "2") (pinfunction "D_2") (pintype "unspecified"))
    )
    (net (code "64") (name "Net-(U16-K)") (class "Default")
      (node (ref "P5") (pin "2") (pinfunction "2_2") (pintype "unspecified"))
      (node (ref "U16") (pin "2") (pinfunction "K_2") (pintype "unspecified"))
    )
    (net (code "65") (name "Net-(U17-A)") (class "Default")
      (node (ref "P6") (pin "1") (pinfunction "1_1") (pintype "unspecified"))
      (node (ref "U17") (pin "1") (pinfunction "A_1") (pintype "unspecified"))
      (node (ref "U19") (pin "2") (pinfunction "D_2") (pintype "unspecified"))
    )
    (net (code "66") (name "Net-(U17-K)") (class "Default")
      (node (ref "P6") (pin "2") (pinfunction "2_2") (pintype "unspecified"))
      (node (ref "U17") (pin "2") (pinfunction "K_2") (pintype "unspecified"))
    )
    (net (code "67") (name "Net-(U18-G)") (class "Default")
      (node (ref "R10") (pin "2") (pinfunction "2_2") (pintype "unspecified"))
      (node (ref "R12") (pin "2") (pinfunction "2_2") (pintype "unspecified"))
      (node (ref "U18") (pin "1") (pinfunction "G_1") (pintype "unspecified"))
    )
    (net (code "68") (name "Net-(U19-G)") (class "Default")
      (node (ref "R11") (pin "2") (pinfunction "2_2") (pintype "unspecified"))
      (node (ref "R13") (pin "2") (pinfunction "2_2") (pintype "unspecified"))
      (node (ref "U19") (pin "1") (pinfunction "G_1") (pintype "unspecified"))
    )
    (net (code "69") (name "Net-(U20-A)") (class "Default")
      (node (ref "P7") (pin "1") (pinfunction "1_1") (pintype "unspecified"))
      (node (ref "U20") (pin "1") (pinfunction "A_1") (pintype "unspecified"))
      (node (ref "U22") (pin "2") (pinfunction "D_2") (pintype "unspecified"))
    )
    (net (code "70") (name "Net-(U20-K)") (class "Default")
      (node (ref "P7") (pin "2") (pinfunction "2_2") (pintype "unspecified"))
      (node (ref "U20") (pin "2") (pinfunction "K_2") (pintype "unspecified"))
    )
    (net (code "71") (name "Net-(U21-A)") (class "Default")
      (node (ref "P8") (pin "1") (pinfunction "1_1") (pintype "unspecified"))
      (node (ref "U21") (pin "1") (pinfunction "A_1") (pintype "unspecified"))
      (node (ref "U23") (pin "2") (pinfunction "D_2") (pintype "unspecified"))
    )
    (net (code "72") (name "Net-(U21-K)") (class "Default")
      (node (ref "P8") (pin "2") (pinfunction "2_2") (pintype "unspecified"))
      (node (ref "U21") (pin "2") (pinfunction "K_2") (pintype "unspecified"))
    )
    (net (code "73") (name "Net-(U22-G)") (class "Default")
      (node (ref "R14") (pin "2") (pinfunction "2_2") (pintype "unspecified"))
      (node (ref "R16") (pin "2") (pinfunction "2_2") (pintype "unspecified"))
      (node (ref "U22") (pin "1") (pinfunction "G_1") (pintype "unspecified"))
    )
    (net (code "74") (name "Net-(U23-G)") (class "Default")
      (node (ref "R15") (pin "2") (pinfunction "2_2") (pintype "unspecified"))
      (node (ref "R17") (pin "2") (pinfunction "2_2") (pintype "unspecified"))
      (node (ref "U23") (pin "1") (pinfunction "G_1") (pintype "unspecified"))
    )
    (net (code "75") (name "Net-(U24-A)") (class "Default")
      (node (ref "P9") (pin "1") (pinfunction "1_1") (pintype "unspecified"))
      (node (ref "U24") (pin "1") (pinfunction "A_1") (pintype "unspecified"))
      (node (ref "U26") (pin "2") (pinfunction "D_2") (pintype "unspecified"))
    )
    (net (code "76") (name "Net-(U24-K)") (class "Default")
      (node (ref "P9") (pin "2") (pinfunction "2_2") (pintype "unspecified"))
      (node (ref "U24") (pin "2") (pinfunction "K_2") (pintype "unspecified"))
    )
    (net (code "77") (name "Net-(U25-A)") (class "Default")
      (node (ref "P10") (pin "1") (pinfunction "1_1") (pintype "unspecified"))
      (node (ref "U25") (pin "1") (pinfunction "A_1") (pintype "unspecified"))
      (node (ref "U27") (pin "2") (pinfunction "D_2") (pintype "unspecified"))
    )
    (net (code "78") (name "Net-(U25-K)") (class "Default")
      (node (ref "P10") (pin "2") (pinfunction "2_2") (pintype "unspecified"))
      (node (ref "U25") (pin "2") (pinfunction "K_2") (pintype "unspecified"))
    )
    (net (code "79") (name "Net-(U26-G)") (class "Default")
      (node (ref "R18") (pin "2") (pinfunction "2_2") (pintype "unspecified"))
      (node (ref "R20") (pin "2") (pinfunction "2_2") (pintype "unspecified"))
      (node (ref "U26") (pin "1") (pinfunction "G_1") (pintype "unspecified"))
    )
    (net (code "80") (name "Net-(U27-G)") (class "Default")
      (node (ref "R19") (pin "2") (pinfunction "2_2") (pintype "unspecified"))
      (node (ref "R21") (pin "2") (pinfunction "2_2") (pintype "unspecified"))
      (node (ref "U27") (pin "1") (pinfunction "G_1") (pintype "unspecified"))
    )
    (net (code "81") (name "Net-(U28-A)") (class "Default")
      (node (ref "P11") (pin "1") (pinfunction "1_1") (pintype "unspecified"))
      (node (ref "U28") (pin "1") (pinfunction "A_1") (pintype "unspecified"))
      (node (ref "U30") (pin "2") (pinfunction "D_2") (pintype "unspecified"))
    )
    (net (code "82") (name "Net-(U28-K)") (class "Default")
      (node (ref "P11") (pin "2") (pinfunction "2_2") (pintype "unspecified"))
      (node (ref "U28") (pin "2") (pinfunction "K_2") (pintype "unspecified"))
    )
    (net (code "83") (name "Net-(U29-A)") (class "Default")
      (node (ref "P12") (pin "1") (pinfunction "1_1") (pintype "unspecified"))
      (node (ref "U29") (pin "1") (pinfunction "A_1") (pintype "unspecified"))
      (node (ref "U31") (pin "2") (pinfunction "D_2") (pintype "unspecified"))
    )
    (net (code "84") (name "Net-(U29-K)") (class "Default")
      (node (ref "P12") (pin "2") (pinfunction "2_2") (pintype "unspecified"))
      (node (ref "U29") (pin "2") (pinfunction "K_2") (pintype "unspecified"))
    )
    (net (code "85") (name "Net-(U30-G)") (class "Default")
      (node (ref "R22") (pin "2") (pinfunction "2_2") (pintype "unspecified"))
      (node (ref "R24") (pin "2") (pinfunction "2_2") (pintype "unspecified"))
      (node (ref "U30") (pin "1") (pinfunction "G_1") (pintype "unspecified"))
    )
    (net (code "86") (name "Net-(U31-G)") (class "Default")
      (node (ref "R23") (pin "2") (pinfunction "2_2") (pintype "unspecified"))
      (node (ref "R25") (pin "2") (pinfunction "2_2") (pintype "unspecified"))
      (node (ref "U31") (pin "1") (pinfunction "G_1") (pintype "unspecified"))
    )
    (net (code "87") (name "Net-(U32-A)") (class "Default")
      (node (ref "P13") (pin "1") (pinfunction "1_1") (pintype "unspecified"))
      (node (ref "U32") (pin "1") (pinfunction "A_1") (pintype "unspecified"))
      (node (ref "U34") (pin "2") (pinfunction "D_2") (pintype "unspecified"))
    )
    (net (code "88") (name "Net-(U32-K)") (class "Default")
      (node (ref "P13") (pin "2") (pinfunction "2_2") (pintype "unspecified"))
      (node (ref "U32") (pin "2") (pinfunction "K_2") (pintype "unspecified"))
    )
    (net (code "89") (name "Net-(U33-A)") (class "Default")
      (node (ref "P14") (pin "1") (pinfunction "1_1") (pintype "unspecified"))
      (node (ref "U33") (pin "1") (pinfunction "A_1") (pintype "unspecified"))
      (node (ref "U35") (pin "2") (pinfunction "D_2") (pintype "unspecified"))
    )
    (net (code "90") (name "Net-(U33-K)") (class "Default")
      (node (ref "P14") (pin "2") (pinfunction "2_2") (pintype "unspecified"))
      (node (ref "U33") (pin "2") (pinfunction "K_2") (pintype "unspecified"))
    )
    (net (code "91") (name "Net-(U34-G)") (class "Default")
      (node (ref "R26") (pin "2") (pinfunction "2_2") (pintype "unspecified"))
      (node (ref "R28") (pin "2") (pinfunction "2_2") (pintype "unspecified"))
      (node (ref "U34") (pin "1") (pinfunction "G_1") (pintype "unspecified"))
    )
    (net (code "92") (name "Net-(U35-G)") (class "Default")
      (node (ref "R27") (pin "2") (pinfunction "2_2") (pintype "unspecified"))
      (node (ref "R29") (pin "2") (pinfunction "2_2") (pintype "unspecified"))
      (node (ref "U35") (pin "1") (pinfunction "G_1") (pintype "unspecified"))
    )
    (net (code "93") (name "Net-(U36-A)") (class "Default")
      (node (ref "P15") (pin "1") (pinfunction "1_1") (pintype "unspecified"))
      (node (ref "U36") (pin "1") (pinfunction "A_1") (pintype "unspecified"))
      (node (ref "U38") (pin "2") (pinfunction "D_2") (pintype "unspecified"))
    )
    (net (code "94") (name "Net-(U36-K)") (class "Default")
      (node (ref "P15") (pin "2") (pinfunction "2_2") (pintype "unspecified"))
      (node (ref "U36") (pin "2") (pinfunction "K_2") (pintype "unspecified"))
    )
    (net (code "95") (name "Net-(U37-A)") (class "Default")
      (node (ref "P16") (pin "1") (pinfunction "1_1") (pintype "unspecified"))
      (node (ref "U37") (pin "1") (pinfunction "A_1") (pintype "unspecified"))
      (node (ref "U39") (pin "2") (pinfunction "D_2") (pintype "unspecified"))
    )
    (net (code "96") (name "Net-(U37-K)") (class "Default")
      (node (ref "P16") (pin "2") (pinfunction "2_2") (pintype "unspecified"))
      (node (ref "U37") (pin "2") (pinfunction "K_2") (pintype "unspecified"))
    )
    (net (code "97") (name "Net-(U38-G)") (class "Default")
      (node (ref "R30") (pin "2") (pinfunction "2_2") (pintype "unspecified"))
      (node (ref "R32") (pin "1") (pinfunction "1_1") (pintype "unspecified"))
      (node (ref "U38") (pin "1") (pinfunction "G_1") (pintype "unspecified"))
    )
    (net (code "98") (name "Net-(U39-G)") (class "Default")
      (node (ref "R31") (pin "2") (pinfunction "2_2") (pintype "unspecified"))
      (node (ref "R33") (pin "2") (pinfunction "2_2") (pintype "unspecified"))
      (node (ref "U39") (pin "1") (pinfunction "G_1") (pintype "unspecified"))
    )
    (net (code "99") (name "Power12V") (class "Default")
      (node (ref "U4") (pin "1") (pinfunction "1_1") (pintype "unspecified"))
    )
    (net (code "100") (name "PowerGND") (class "Default")
      (node (ref "U10") (pin "3") (pinfunction "S_3") (pintype "unspecified"))
      (node (ref "U11") (pin "3") (pinfunction "S_3") (pintype "unspecified"))
      (node (ref "U14") (pin "3") (pinfunction "S_3") (pintype "unspecified"))
      (node (ref "U15") (pin "3") (pinfunction "S_3") (pintype "unspecified"))
      (node (ref "U18") (pin "3") (pinfunction "S_3") (pintype "unspecified"))
      (node (ref "U19") (pin "3") (pinfunction "S_3") (pintype "unspecified"))
      (node (ref "U22") (pin "3") (pinfunction "S_3") (pintype "unspecified"))
      (node (ref "U23") (pin "3") (pinfunction "S_3") (pintype "unspecified"))
      (node (ref "U26") (pin "3") (pinfunction "S_3") (pintype "unspecified"))
      (node (ref "U27") (pin "3") (pinfunction "S_3") (pintype "unspecified"))
      (node (ref "U30") (pin "3") (pinfunction "S_3") (pintype "unspecified"))
      (node (ref "U31") (pin "3") (pinfunction "S_3") (pintype "unspecified"))
      (node (ref "U34") (pin "3") (pinfunction "S_3") (pintype "unspecified"))
      (node (ref "U35") (pin "3") (pinfunction "S_3") (pintype "unspecified"))
      (node (ref "U38") (pin "3") (pinfunction "S_3") (pintype "unspecified"))
      (node (ref "U39") (pin "3") (pinfunction "S_3") (pintype "unspecified"))
    )
    (net (code "101") (name "unconnected-(U4-Pad2)") (class "Default")
      (node (ref "U4") (pin "2") (pinfunction "2_2") (pintype "unspecified+no_connect"))
    )
    (net (code "102") (name "unconnected-(U9-3V3-Pad3.3V)") (class "Default")
      (node (ref "U9") (pin "3.3V") (pinfunction "3V3_3.3V") (pintype "bidirectional+no_connect"))
    )
    (net (code "103") (name "unconnected-(U9-13_PWM_SCK_CRX1_LED-Pad13)") (class "Default")
      (node (ref "U9") (pin "13") (pinfunction "13_PWM_SCK_CRX1_LED_13") (pintype "bidirectional"))
    )
    (net (code "104") (name "unconnected-(U9-PadAGND)") (class "Default")
      (node (ref "U9") (pin "AGND") (pinfunction "AGND_AGND") (pintype "bidirectional+no_connect"))
    )
  )
)
